# Sheet1.net
KiCad netlist of a schematic drawn in Altium Designer
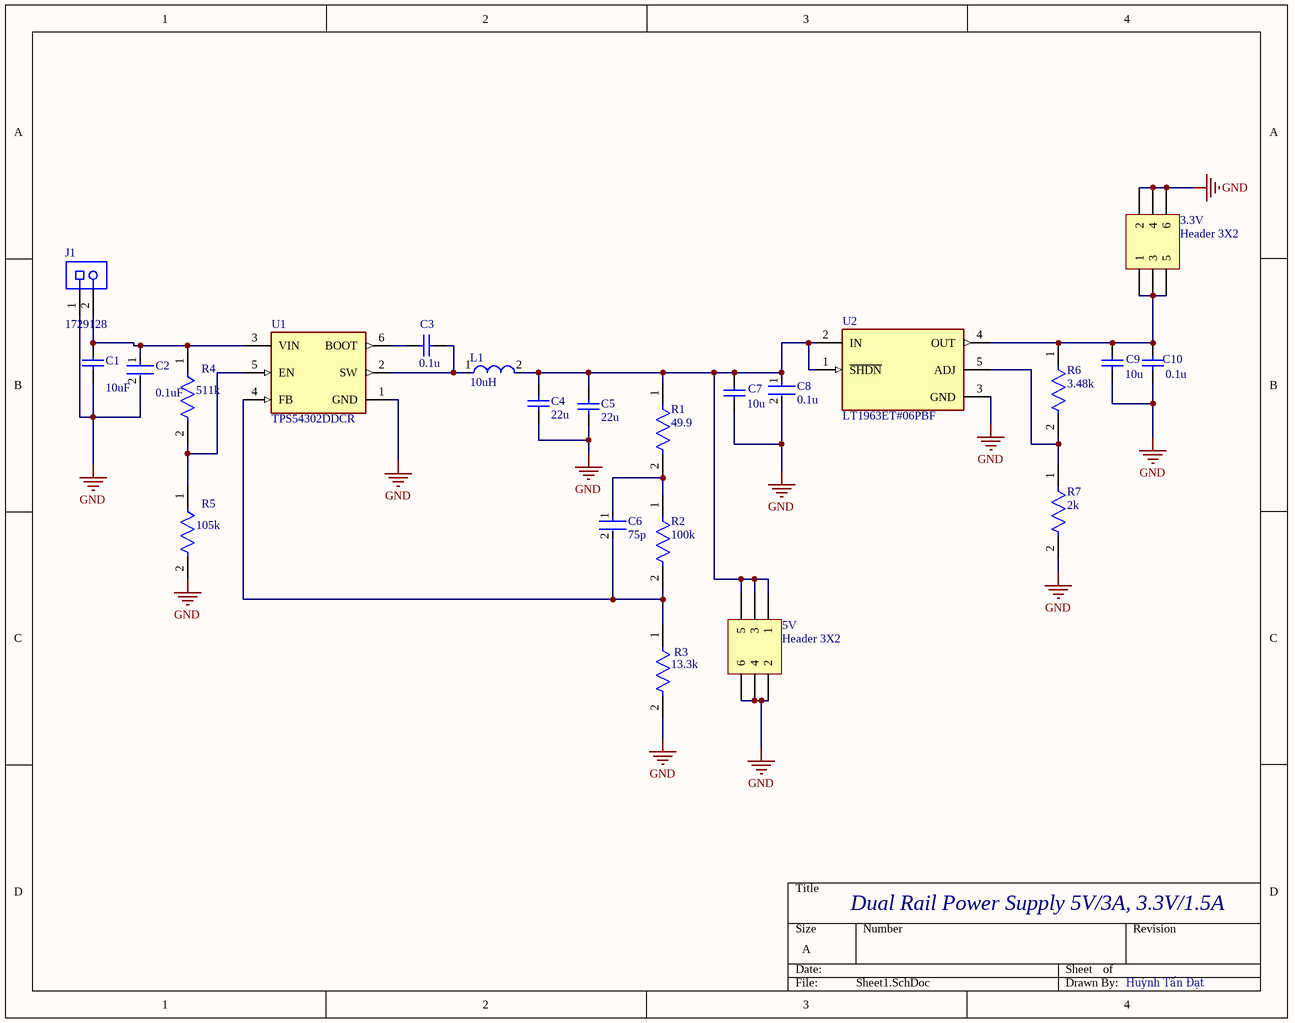
[diagram p0: Sheet1.SchDoc]

(export (version "E")
  (design (tool "Eeschema 10.0.6"))
  (components
    (comp (ref "3.3V")
      (value "Header 3X2")
      (footprint "HDR2X3")
      (description "Header, 3-Pin, Dual row")
      (fields (field (name "PUBLISHER") "Altium Limited"))
      (libsource (lib "Miscellaneous Connectors") (part "Header 3X2"))
    )
    (comp (ref "5V")
      (value "Header 3X2")
      (footprint "HDR2X3")
      (description "Header, 3-Pin, Dual row")
      (fields (field (name "PUBLISHER") "Altium Limited"))
      (libsource (lib "") (part "Header 3X2_1"))
    )
    (comp (ref "C1")
      (value "10uF")
      (footprint "CAPC1206(3216)170_N")
      (description "CAP 560nF 25V ±5% 1206 (3216 Metric) Thickness 1.7mm SMD")
      (fields (field (name "TOLERANCE") "Â±5%"))
      (libsource (lib "Altium Content Vault") (part "CAP"))
    )
    (comp (ref "C2")
      (value "0.1uF")
      (footprint "FP-C0603C-CF-MFG")
      (description "C0603 300 pF X8R 30ppm/°C 1.00% 10 V")
      (fields
        (field (name "MANUFACTURER PART NUMBER") "C0603C301F8HACTU")
        (field (name "OCTOPART") "https://octopart.com/c0603c301f8hactu-kemet-88725572")
      )
      (libsource (lib "Altium Content Vault") (part "b4654b650e69147ec39a6b967a45e02"))
    )
    (comp (ref "C3")
      (value "0.1u")
      (footprint "CAPC1206(3216)170_N")
      (description "CAP 560nF 25V ±5% 1206 (3216 Metric) Thickness 1.7mm SMD")
      (fields (field (name "TOLERANCE") "Â±5%"))
      (libsource (lib "Altium Content Vault") (part "CAP"))
    )
    (comp (ref "C4")
      (value "22u")
      (footprint "CAPC1206(3216)170_N")
      (description "CAP 560nF 25V ±5% 1206 (3216 Metric) Thickness 1.7mm SMD")
      (fields (field (name "TOLERANCE") "Â±5%"))
      (libsource (lib "Altium Content Vault") (part "CAP"))
    )
    (comp (ref "C5")
      (value "22u")
      (footprint "CAPC1206(3216)170_N")
      (description "CAP 560nF 25V ±5% 1206 (3216 Metric) Thickness 1.7mm SMD")
      (fields (field (name "TOLERANCE") "Â±5%"))
      (libsource (lib "Altium Content Vault") (part "CAP"))
    )
    (comp (ref "C6")
      (value "75p")
      (footprint "FP-C0603C-CF-MFG")
      (description "C0603 300 pF X8R 30ppm/°C 1.00% 10 V")
      (fields
        (field (name "MANUFACTURER PART NUMBER") "C0603C301F8HACTU")
        (field (name "OCTOPART") "https://octopart.com/c0603c301f8hactu-kemet-88725572")
      )
      (libsource (lib "Altium Content Vault") (part "b4654b650e69147ec39a6b967a45e02"))
    )
    (comp (ref "C7")
      (value "10u")
      (footprint "CAPC1206(3216)170_N")
      (description "CAP 560nF 25V ±5% 1206 (3216 Metric) Thickness 1.7mm SMD")
      (fields (field (name "TOLERANCE") "Â±5%"))
      (libsource (lib "Altium Content Vault") (part "CAP"))
    )
    (comp (ref "C8")
      (value "0.1u")
      (footprint "FP-C0603C-CF-MFG")
      (description "C0603 300 pF X8R 30ppm/°C 1.00% 10 V")
      (fields
        (field (name "MANUFACTURER PART NUMBER") "C0603C301F8HACTU")
        (field (name "OCTOPART") "https://octopart.com/c0603c301f8hactu-kemet-88725572")
      )
      (libsource (lib "Altium Content Vault") (part "b4654b650e69147ec39a6b967a45e02"))
    )
    (comp (ref "C9")
      (value "10u")
      (footprint "CAPC1206(3216)170_N")
      (description "CAP 560nF 25V ±5% 1206 (3216 Metric) Thickness 1.7mm SMD")
      (fields (field (name "TOLERANCE") "Â±5%"))
      (libsource (lib "Altium Content Vault") (part "CAP"))
    )
    (comp (ref "C10")
      (value "0.1u")
      (footprint "CAPC1206(3216)170_N")
      (description "CAP 560nF 25V ±5% 1206 (3216 Metric) Thickness 1.7mm SMD")
      (fields (field (name "TOLERANCE") "Â±5%"))
      (libsource (lib "Altium Content Vault") (part "CAP"))
    )
    (comp (ref "J1")
      (value "1729128")
      (footprint "PHOE-1729128-2_V")
      (description "PCB Terminal Block, 13.5 A, 400 V, 2-Pin THD, RoHS, Bulk")
      (fields (field (name "MANUFACTURER") "Phoenix Contact"))
      (libsource (lib "Altium Content Vault") (part "CN-2P-F-R2"))
    )
    (comp (ref "L1")
      (value "10uH")
      (footprint "FP-IHLP-2525CZ-FP_2_413x3-MFG")
      (description "Commercial Inductors, High Saturation Series, 5 % DCR Tolerance 10uH 3A 97.71mΩ 20%")
      (fields (field (name "TOLERANCE") "20%"))
      (libsource (lib "Altium Content Vault") (part "725321dda6339637d4d059423bc1c3c"))
    )
    (comp (ref "R1")
      (value "49.9")
      (footprint "FP-TFCR0805-IPC_C")
      (description "RES Thin Film,  2kΩ, 0.1%, 0.1W, 25ppm/°C, 0805")
      (libsource (lib "Altium Content Vault") (part "1029c3af85768c4190bb7ad29bc67b5"))
    )
    (comp (ref "R2")
      (value "100k")
      (footprint "FP-TFCR0805-IPC_C")
      (description "RES Thin Film,  2kΩ, 0.1%, 0.1W, 25ppm/°C, 0805")
      (libsource (lib "Altium Content Vault") (part "1029c3af85768c4190bb7ad29bc67b5"))
    )
    (comp (ref "R3")
      (value "13.3k")
      (footprint "FP-TFCR0805-IPC_C")
      (description "RES Thin Film,  2kΩ, 0.1%, 0.1W, 25ppm/°C, 0805")
      (libsource (lib "Altium Content Vault") (part "1029c3af85768c4190bb7ad29bc67b5"))
    )
    (comp (ref "R4")
      (value "511k")
      (footprint "FP-TFCR0805-IPC_C")
      (description "RES Thin Film,  2kΩ, 0.1%, 0.1W, 25ppm/°C, 0805")
      (libsource (lib "Altium Content Vault") (part "1029c3af85768c4190bb7ad29bc67b5"))
    )
    (comp (ref "R5")
      (value "105k")
      (footprint "FP-TFCR0805-IPC_C")
      (description "RES Thin Film,  2kΩ, 0.1%, 0.1W, 25ppm/°C, 0805")
      (libsource (lib "Altium Content Vault") (part "1029c3af85768c4190bb7ad29bc67b5"))
    )
    (comp (ref "R6")
      (value "3.48k")
      (footprint "FP-TFCR0805-IPC_C")
      (description "RES Thin Film,  2kΩ, 0.1%, 0.1W, 25ppm/°C, 0805")
      (libsource (lib "Altium Content Vault") (part "1029c3af85768c4190bb7ad29bc67b5"))
    )
    (comp (ref "R7")
      (value "2k")
      (footprint "FP-TFCR0805-IPC_C")
      (description "RES Thin Film,  2kΩ, 0.1%, 0.1W, 25ppm/°C, 0805")
      (libsource (lib "Altium Content Vault") (part "1029c3af85768c4190bb7ad29bc67b5"))
    )
    (comp (ref "U1")
      (value "TPS54302DDCR")
      (footprint "FP-DDC0006A-MFG")
      (description "IC REG BUCK ADJ 3A TSOT23-6")
      (fields
        (field (name "MANUFACTURER") "Texas Instruments")
        (field (name "OCTOPART") "https://octopart.com/tps54302ddcr-texas+instruments-74209025")
      )
      (libsource (lib "Altium Content Vault") (part "e6e62595b56d4ede9a2c24ebe42f01f"))
    )
    (comp (ref "U2")
      (value "LT1963ET#06PBF")
      (footprint "FP-T-5-05-08-1421-MFG")
      (description "IC REG LIN POS ADJ 1.5A TO220-5")
      (libsource (lib "Altium Content Vault") (part "4949f3cacc6fdae42fc18d117f71ed5"))
    )
  )
  (nets
    (net (code "1") (name "GND") (class "Default")
      (node (ref "3.3V") (pin "2") (pinfunction "2_2") (pintype "passive"))
      (node (ref "3.3V") (pin "4") (pinfunction "4_4") (pintype "passive"))
      (node (ref "3.3V") (pin "6") (pinfunction "6_6") (pintype "passive"))
      (node (ref "5V") (pin "2") (pinfunction "2_2") (pintype "passive"))
      (node (ref "5V") (pin "4") (pinfunction "4_4") (pintype "passive"))
      (node (ref "5V") (pin "6") (pinfunction "6_6") (pintype "passive"))
      (node (ref "C1") (pin "1") (pinfunction "1_1") (pintype "passive"))
      (node (ref "C10") (pin "1") (pinfunction "1_1") (pintype "passive"))
      (node (ref "C2") (pin "2") (pinfunction "2_2") (pintype "passive"))
      (node (ref "C4") (pin "2") (pinfunction "2_2") (pintype "passive"))
      (node (ref "C5") (pin "2") (pinfunction "2_2") (pintype "passive"))
      (node (ref "C7") (pin "1") (pinfunction "1_1") (pintype "passive"))
      (node (ref "C8") (pin "2") (pinfunction "2_2") (pintype "passive"))
      (node (ref "C9") (pin "1") (pinfunction "1_1") (pintype "passive"))
      (node (ref "J1") (pin "1") (pinfunction "1_1") (pintype "passive"))
      (node (ref "R3") (pin "2") (pinfunction "2_2") (pintype "passive"))
      (node (ref "R5") (pin "2") (pinfunction "2_2") (pintype "passive"))
      (node (ref "R7") (pin "2") (pinfunction "2_2") (pintype "passive"))
      (node (ref "U1") (pin "1") (pinfunction "GND_1") (pintype "power_in"))
      (node (ref "U2") (pin "3") (pinfunction "GND_3") (pintype "power_in"))
    )
    (net (code "2") (name "Net-(C6-Pad1)") (class "Default")
      (node (ref "C6") (pin "1") (pinfunction "1_1") (pintype "passive"))
      (node (ref "R1") (pin "2") (pinfunction "2_2") (pintype "passive"))
      (node (ref "R2") (pin "1") (pinfunction "1_1") (pintype "passive"))
    )
    (net (code "3") (name "Net-(U1-BOOT)") (class "Default")
      (node (ref "C3") (pin "2") (pinfunction "2_2") (pintype "passive"))
      (node (ref "U1") (pin "6") (pinfunction "BOOT_6") (pintype "output"))
    )
    (net (code "4") (name "Net-(U1-EN)") (class "Default")
      (node (ref "R4") (pin "2") (pinfunction "2_2") (pintype "passive"))
      (node (ref "R5") (pin "1") (pinfunction "1_1") (pintype "passive"))
      (node (ref "U1") (pin "5") (pinfunction "EN_5") (pintype "input"))
    )
    (net (code "5") (name "Net-(U1-FB)") (class "Default")
      (node (ref "C6") (pin "2") (pinfunction "2_2") (pintype "passive"))
      (node (ref "R2") (pin "2") (pinfunction "2_2") (pintype "passive"))
      (node (ref "R3") (pin "1") (pinfunction "1_1") (pintype "passive"))
      (node (ref "U1") (pin "4") (pinfunction "FB_4") (pintype "input"))
    )
    (net (code "6") (name "Net-(U1-SW)") (class "Default")
      (node (ref "C3") (pin "1") (pinfunction "1_1") (pintype "passive"))
      (node (ref "L1") (pin "1") (pinfunction "1_1") (pintype "passive"))
      (node (ref "U1") (pin "2") (pinfunction "SW_2") (pintype "output"))
    )
    (net (code "7") (name "Net-(U1-VIN)") (class "Default")
      (node (ref "C1") (pin "2") (pinfunction "2_2") (pintype "passive"))
      (node (ref "C2") (pin "1") (pinfunction "1_1") (pintype "passive"))
      (node (ref "J1") (pin "2") (pinfunction "2_2") (pintype "passive"))
      (node (ref "R4") (pin "1") (pinfunction "1_1") (pintype "passive"))
      (node (ref "U1") (pin "3") (pinfunction "VIN_3") (pintype "power_in"))
    )
    (net (code "8") (name "Net-(U2-ADJ)") (class "Default")
      (node (ref "R6") (pin "2") (pinfunction "2_2") (pintype "passive"))
      (node (ref "R7") (pin "1") (pinfunction "1_1") (pintype "passive"))
      (node (ref "U2") (pin "5") (pinfunction "ADJ_5") (pintype "passive"))
    )
    (net (code "9") (name "Net-(U2-IN)") (class "Default")
      (node (ref "5V") (pin "1") (pinfunction "1_1") (pintype "passive"))
      (node (ref "5V") (pin "3") (pinfunction "3_3") (pintype "passive"))
      (node (ref "5V") (pin "5") (pinfunction "5_5") (pintype "passive"))
      (node (ref "C4") (pin "1") (pinfunction "1_1") (pintype "passive"))
      (node (ref "C5") (pin "1") (pinfunction "1_1") (pintype "passive"))
      (node (ref "C7") (pin "2") (pinfunction "2_2") (pintype "passive"))
      (node (ref "C8") (pin "1") (pinfunction "1_1") (pintype "passive"))
      (node (ref "L1") (pin "2") (pinfunction "2_2") (pintype "passive"))
      (node (ref "R1") (pin "1") (pinfunction "1_1") (pintype "passive"))
      (node (ref "U2") (pin "1") (pinfunction "~{SHDN}_1") (pintype "input"))
      (node (ref "U2") (pin "2") (pinfunction "IN_2") (pintype "power_in"))
    )
    (net (code "10") (name "Net-(U2-OUT)") (class "Default")
      (node (ref "3.3V") (pin "1") (pinfunction "1_1") (pintype "passive"))
      (node (ref "3.3V") (pin "3") (pinfunction "3_3") (pintype "passive"))
      (node (ref "3.3V") (pin "5") (pinfunction "5_5") (pintype "passive"))
      (node (ref "C10") (pin "2") (pinfunction "2_2") (pintype "passive"))
      (node (ref "C9") (pin "2") (pinfunction "2_2") (pintype "passive"))
      (node (ref "R6") (pin "1") (pinfunction "1_1") (pintype "passive"))
      (node (ref "U2") (pin "4") (pinfunction "OUT_4") (pintype "output"))
    )
  )
)
